# UM6650C.net
KiCad netlist of a schematic drawn in EAGLE
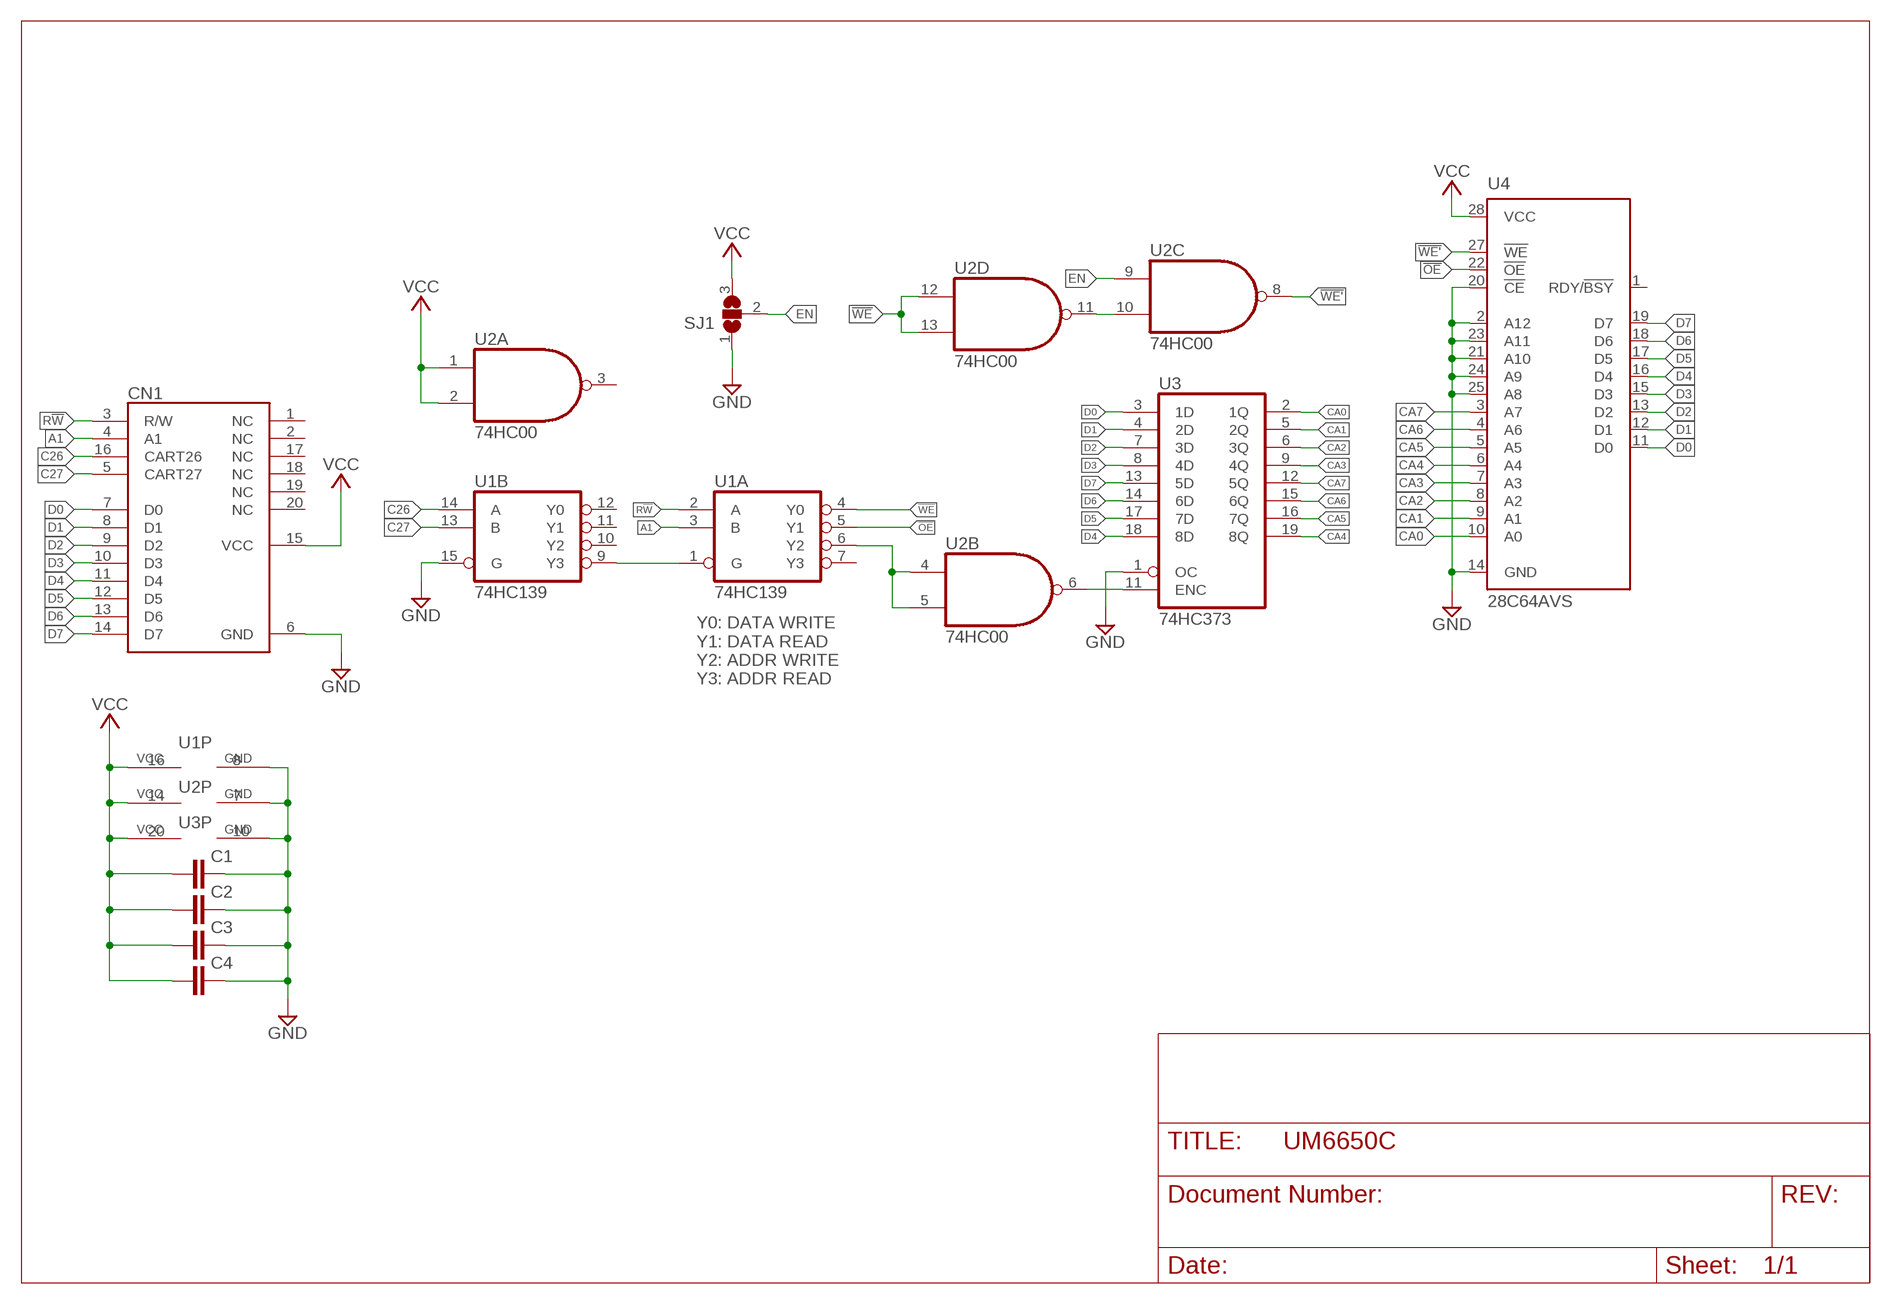
[diagram p0: schematic, sheet 1]

(export (version "E")
  (design (tool "Eeschema 10.0.6"))
  (components
    (comp (ref "C1")
      (value "C-EUC0603")
      (footprint "eagle-import:C0603")
      (libsource (lib "eagle-import") (part "C-EUC0603"))
    )
    (comp (ref "C2")
      (value "C-EUC0603")
      (footprint "eagle-import:C0603")
      (libsource (lib "eagle-import") (part "C-EUC0603"))
    )
    (comp (ref "C3")
      (value "C-EUC0603")
      (footprint "eagle-import:C0603")
      (libsource (lib "eagle-import") (part "C-EUC0603"))
    )
    (comp (ref "C4")
      (value "C-EUC0603")
      (footprint "eagle-import:C0603")
      (libsource (lib "eagle-import") (part "C-EUC0603"))
    )
    (comp (ref "CN1")
      (value "UM6650")
      (footprint "eagle-import:DIL20")
      (libsource (lib "eagle-import") (part "UM6650"))
    )
    (comp (ref "SJ1")
      (value "SJ2W")
      (footprint "eagle-import:SJ_2")
      (libsource (lib "eagle-import") (part "SJ2W"))
    )
    (comp (ref "U1")
      (value "74HC139")
      (footprint "eagle-import:TSSOP16")
      (libsource (lib "eagle-import") (part "74139PW"))
    )
    (comp (ref "U2")
      (value "74HC00")
      (footprint "eagle-import:TSSOP14")
      (libsource (lib "eagle-import") (part "7400PW"))
    )
    (comp (ref "U3")
      (value "74HC373")
      (footprint "eagle-import:TSSOP20")
      (libsource (lib "eagle-import") (part "74373PW"))
    )
    (comp (ref "U4")
      (value "28C64AVS")
      (footprint "eagle-import:VSOP28-8X13")
      (libsource (lib "eagle-import") (part "2864AVSC"))
    )
  )
  (nets
    (net (code "1") (name "/R~{W}") (class "Default")
      (node (ref "CN1") (pin "3") (pinfunction "R/W_3") (pintype "input"))
      (node (ref "U1") (pin "2") (pinfunction "A_2") (pintype "input"))
    )
    (net (code "2") (name "/~{OE}") (class "Default")
      (node (ref "U1") (pin "5") (pinfunction "Y1_5") (pintype "output"))
      (node (ref "U4") (pin "22") (pinfunction "~{OE}_22") (pintype "input"))
    )
    (net (code "3") (name "/~{WE'}") (class "Default")
      (node (ref "U2") (pin "8") (pinfunction "O_8") (pintype "output"))
      (node (ref "U4") (pin "27") (pinfunction "~{WE}_27") (pintype "input"))
    )
    (net (code "4") (name "/~{WE}") (class "Default")
      (node (ref "U1") (pin "4") (pinfunction "Y0_4") (pintype "output"))
      (node (ref "U2") (pin "12") (pinfunction "I0_12") (pintype "input"))
      (node (ref "U2") (pin "13") (pinfunction "I1_13") (pintype "input"))
    )
    (net (code "5") (name "A1") (class "Default")
      (node (ref "CN1") (pin "4") (pinfunction "A1_4") (pintype "input"))
      (node (ref "U1") (pin "3") (pinfunction "B_3") (pintype "input"))
    )
    (net (code "6") (name "C26") (class "Default")
      (node (ref "CN1") (pin "16") (pinfunction "CART26_16") (pintype "bidirectional"))
      (node (ref "U1") (pin "14") (pinfunction "A_14") (pintype "input"))
    )
    (net (code "7") (name "C27") (class "Default")
      (node (ref "CN1") (pin "5") (pinfunction "CART27_5") (pintype "bidirectional"))
      (node (ref "U1") (pin "13") (pinfunction "B_13") (pintype "input"))
    )
    (net (code "8") (name "CA0") (class "Default")
      (node (ref "U3") (pin "2") (pinfunction "1Q_2") (pintype "tri_state"))
      (node (ref "U4") (pin "10") (pinfunction "A0_10") (pintype "input"))
    )
    (net (code "9") (name "CA1") (class "Default")
      (node (ref "U3") (pin "5") (pinfunction "2Q_5") (pintype "tri_state"))
      (node (ref "U4") (pin "9") (pinfunction "A1_9") (pintype "input"))
    )
    (net (code "10") (name "CA2") (class "Default")
      (node (ref "U3") (pin "6") (pinfunction "3Q_6") (pintype "tri_state"))
      (node (ref "U4") (pin "8") (pinfunction "A2_8") (pintype "input"))
    )
    (net (code "11") (name "CA3") (class "Default")
      (node (ref "U3") (pin "9") (pinfunction "4Q_9") (pintype "tri_state"))
      (node (ref "U4") (pin "7") (pinfunction "A3_7") (pintype "input"))
    )
    (net (code "12") (name "CA4") (class "Default")
      (node (ref "U3") (pin "19") (pinfunction "8Q_19") (pintype "tri_state"))
      (node (ref "U4") (pin "6") (pinfunction "A4_6") (pintype "input"))
    )
    (net (code "13") (name "CA5") (class "Default")
      (node (ref "U3") (pin "16") (pinfunction "7Q_16") (pintype "tri_state"))
      (node (ref "U4") (pin "5") (pinfunction "A5_5") (pintype "input"))
    )
    (net (code "14") (name "CA6") (class "Default")
      (node (ref "U3") (pin "15") (pinfunction "6Q_15") (pintype "tri_state"))
      (node (ref "U4") (pin "4") (pinfunction "A6_4") (pintype "input"))
    )
    (net (code "15") (name "CA7") (class "Default")
      (node (ref "U3") (pin "12") (pinfunction "5Q_12") (pintype "tri_state"))
      (node (ref "U4") (pin "3") (pinfunction "A7_3") (pintype "input"))
    )
    (net (code "16") (name "D0") (class "Default")
      (node (ref "CN1") (pin "7") (pinfunction "D0_7") (pintype "bidirectional"))
      (node (ref "U3") (pin "3") (pinfunction "1D_3") (pintype "input"))
      (node (ref "U4") (pin "11") (pinfunction "D0_11") (pintype "tri_state"))
    )
    (net (code "17") (name "D1") (class "Default")
      (node (ref "CN1") (pin "8") (pinfunction "D1_8") (pintype "bidirectional"))
      (node (ref "U3") (pin "4") (pinfunction "2D_4") (pintype "input"))
      (node (ref "U4") (pin "12") (pinfunction "D1_12") (pintype "tri_state"))
    )
    (net (code "18") (name "D2") (class "Default")
      (node (ref "CN1") (pin "9") (pinfunction "D2_9") (pintype "bidirectional"))
      (node (ref "U3") (pin "7") (pinfunction "3D_7") (pintype "input"))
      (node (ref "U4") (pin "13") (pinfunction "D2_13") (pintype "tri_state"))
    )
    (net (code "19") (name "D3") (class "Default")
      (node (ref "CN1") (pin "10") (pinfunction "D3_10") (pintype "bidirectional"))
      (node (ref "U3") (pin "8") (pinfunction "4D_8") (pintype "input"))
      (node (ref "U4") (pin "15") (pinfunction "D3_15") (pintype "tri_state"))
    )
    (net (code "20") (name "D4") (class "Default")
      (node (ref "CN1") (pin "11") (pinfunction "D4_11") (pintype "bidirectional"))
      (node (ref "U3") (pin "18") (pinfunction "8D_18") (pintype "input"))
      (node (ref "U4") (pin "16") (pinfunction "D4_16") (pintype "tri_state"))
    )
    (net (code "21") (name "D5") (class "Default")
      (node (ref "CN1") (pin "12") (pinfunction "D5_12") (pintype "bidirectional"))
      (node (ref "U3") (pin "17") (pinfunction "7D_17") (pintype "input"))
      (node (ref "U4") (pin "17") (pinfunction "D5_17") (pintype "tri_state"))
    )
    (net (code "22") (name "D6") (class "Default")
      (node (ref "CN1") (pin "13") (pinfunction "D6_13") (pintype "bidirectional"))
      (node (ref "U3") (pin "14") (pinfunction "6D_14") (pintype "input"))
      (node (ref "U4") (pin "18") (pinfunction "D6_18") (pintype "tri_state"))
    )
    (net (code "23") (name "D7") (class "Default")
      (node (ref "CN1") (pin "14") (pinfunction "D7_14") (pintype "bidirectional"))
      (node (ref "U3") (pin "13") (pinfunction "5D_13") (pintype "input"))
      (node (ref "U4") (pin "19") (pinfunction "D7_19") (pintype "tri_state"))
    )
    (net (code "24") (name "EN") (class "Default")
      (node (ref "SJ1") (pin "2") (pinfunction "2_2") (pintype "passive"))
      (node (ref "U2") (pin "9") (pinfunction "I0_9") (pintype "input"))
    )
    (net (code "25") (name "GND") (class "Default")
      (node (ref "C1") (pin "2") (pinfunction "2_2") (pintype "passive"))
      (node (ref "C2") (pin "2") (pinfunction "2_2") (pintype "passive"))
      (node (ref "C3") (pin "2") (pinfunction "2_2") (pintype "passive"))
      (node (ref "C4") (pin "2") (pinfunction "2_2") (pintype "passive"))
      (node (ref "CN1") (pin "6") (pinfunction "GND_6") (pintype "power_in"))
      (node (ref "SJ1") (pin "1") (pinfunction "1_1") (pintype "passive"))
      (node (ref "U1") (pin "15") (pinfunction "G_15") (pintype "input"))
      (node (ref "U1") (pin "8") (pinfunction "GND_8") (pintype "power_in"))
      (node (ref "U2") (pin "7") (pinfunction "GND_7") (pintype "power_in"))
      (node (ref "U3") (pin "1") (pinfunction "OC_1") (pintype "input"))
      (node (ref "U3") (pin "10") (pinfunction "GND_10") (pintype "power_in"))
      (node (ref "U4") (pin "14") (pinfunction "GND_14") (pintype "power_in"))
      (node (ref "U4") (pin "2") (pinfunction "A12_2") (pintype "input"))
      (node (ref "U4") (pin "20") (pinfunction "~{CE}_20") (pintype "input"))
      (node (ref "U4") (pin "21") (pinfunction "A10_21") (pintype "input"))
      (node (ref "U4") (pin "23") (pinfunction "A11_23") (pintype "input"))
      (node (ref "U4") (pin "24") (pinfunction "A9_24") (pintype "input"))
      (node (ref "U4") (pin "25") (pinfunction "A8_25") (pintype "input"))
    )
    (net (code "26") (name "Net-(U1A-G)") (class "Default")
      (node (ref "U1") (pin "1") (pinfunction "G_1") (pintype "input"))
      (node (ref "U1") (pin "9") (pinfunction "Y3_9") (pintype "output"))
    )
    (net (code "27") (name "Net-(U1A-Y2)") (class "Default")
      (node (ref "U1") (pin "6") (pinfunction "Y2_6") (pintype "output"))
      (node (ref "U2") (pin "4") (pinfunction "I0_4") (pintype "input"))
      (node (ref "U2") (pin "5") (pinfunction "I1_5") (pintype "input"))
    )
    (net (code "28") (name "Net-(U2B-O)") (class "Default")
      (node (ref "U2") (pin "6") (pinfunction "O_6") (pintype "output"))
      (node (ref "U3") (pin "11") (pinfunction "ENC_11") (pintype "input"))
    )
    (net (code "29") (name "Net-(U2C-I1)") (class "Default")
      (node (ref "U2") (pin "10") (pinfunction "I1_10") (pintype "input"))
      (node (ref "U2") (pin "11") (pinfunction "O_11") (pintype "output"))
    )
    (net (code "30") (name "VCC") (class "Default")
      (node (ref "C1") (pin "1") (pinfunction "1_1") (pintype "passive"))
      (node (ref "C2") (pin "1") (pinfunction "1_1") (pintype "passive"))
      (node (ref "C3") (pin "1") (pinfunction "1_1") (pintype "passive"))
      (node (ref "C4") (pin "1") (pinfunction "1_1") (pintype "passive"))
      (node (ref "CN1") (pin "15") (pinfunction "VCC_15") (pintype "power_in"))
      (node (ref "SJ1") (pin "3") (pinfunction "3_3") (pintype "passive"))
      (node (ref "U1") (pin "16") (pinfunction "VCC_16") (pintype "power_in"))
      (node (ref "U2") (pin "1") (pinfunction "I0_1") (pintype "input"))
      (node (ref "U2") (pin "14") (pinfunction "VCC_14") (pintype "power_in"))
      (node (ref "U2") (pin "2") (pinfunction "I1_2") (pintype "input"))
      (node (ref "U3") (pin "20") (pinfunction "VCC_20") (pintype "power_in"))
      (node (ref "U4") (pin "28") (pinfunction "VCC_28") (pintype "power_in"))
    )
    (net (code "31") (name "unconnected-(CN1-NC-Pad1)") (class "Default")
      (node (ref "CN1") (pin "1") (pinfunction "NC_1") (pintype "no_connect"))
    )
    (net (code "32") (name "unconnected-(CN1-NC-Pad2)") (class "Default")
      (node (ref "CN1") (pin "2") (pinfunction "NC_2") (pintype "no_connect"))
    )
    (net (code "33") (name "unconnected-(CN1-NC-Pad17)") (class "Default")
      (node (ref "CN1") (pin "17") (pinfunction "NC_17") (pintype "no_connect"))
    )
    (net (code "34") (name "unconnected-(CN1-NC-Pad18)") (class "Default")
      (node (ref "CN1") (pin "18") (pinfunction "NC_18") (pintype "no_connect"))
    )
    (net (code "35") (name "unconnected-(CN1-NC-Pad19)") (class "Default")
      (node (ref "CN1") (pin "19") (pinfunction "NC_19") (pintype "no_connect"))
    )
    (net (code "36") (name "unconnected-(CN1-NC-Pad20)") (class "Default")
      (node (ref "CN1") (pin "20") (pinfunction "NC_20") (pintype "no_connect"))
    )
    (net (code "37") (name "unconnected-(U1A-Y3-Pad7)") (class "Default")
      (node (ref "U1") (pin "7") (pinfunction "Y3_7") (pintype "output"))
    )
    (net (code "38") (name "unconnected-(U1B-Y0-Pad12)") (class "Default")
      (node (ref "U1") (pin "12") (pinfunction "Y0_12") (pintype "output"))
    )
    (net (code "39") (name "unconnected-(U1B-Y1-Pad11)") (class "Default")
      (node (ref "U1") (pin "11") (pinfunction "Y1_11") (pintype "output"))
    )
    (net (code "40") (name "unconnected-(U1B-Y2-Pad10)") (class "Default")
      (node (ref "U1") (pin "10") (pinfunction "Y2_10") (pintype "output"))
    )
    (net (code "41") (name "unconnected-(U2A-O-Pad3)") (class "Default")
      (node (ref "U2") (pin "3") (pinfunction "O_3") (pintype "output"))
    )
    (net (code "42") (name "unconnected-(U4-RDY{slash}~{BSY}-Pad1)") (class "Default")
      (node (ref "U4") (pin "1") (pinfunction "RDY/~{BSY}_1") (pintype "output"))
    )
  )
)
